# usbMIDI2CV_MC.net
KiCad netlist of a schematic drawn in EAGLE
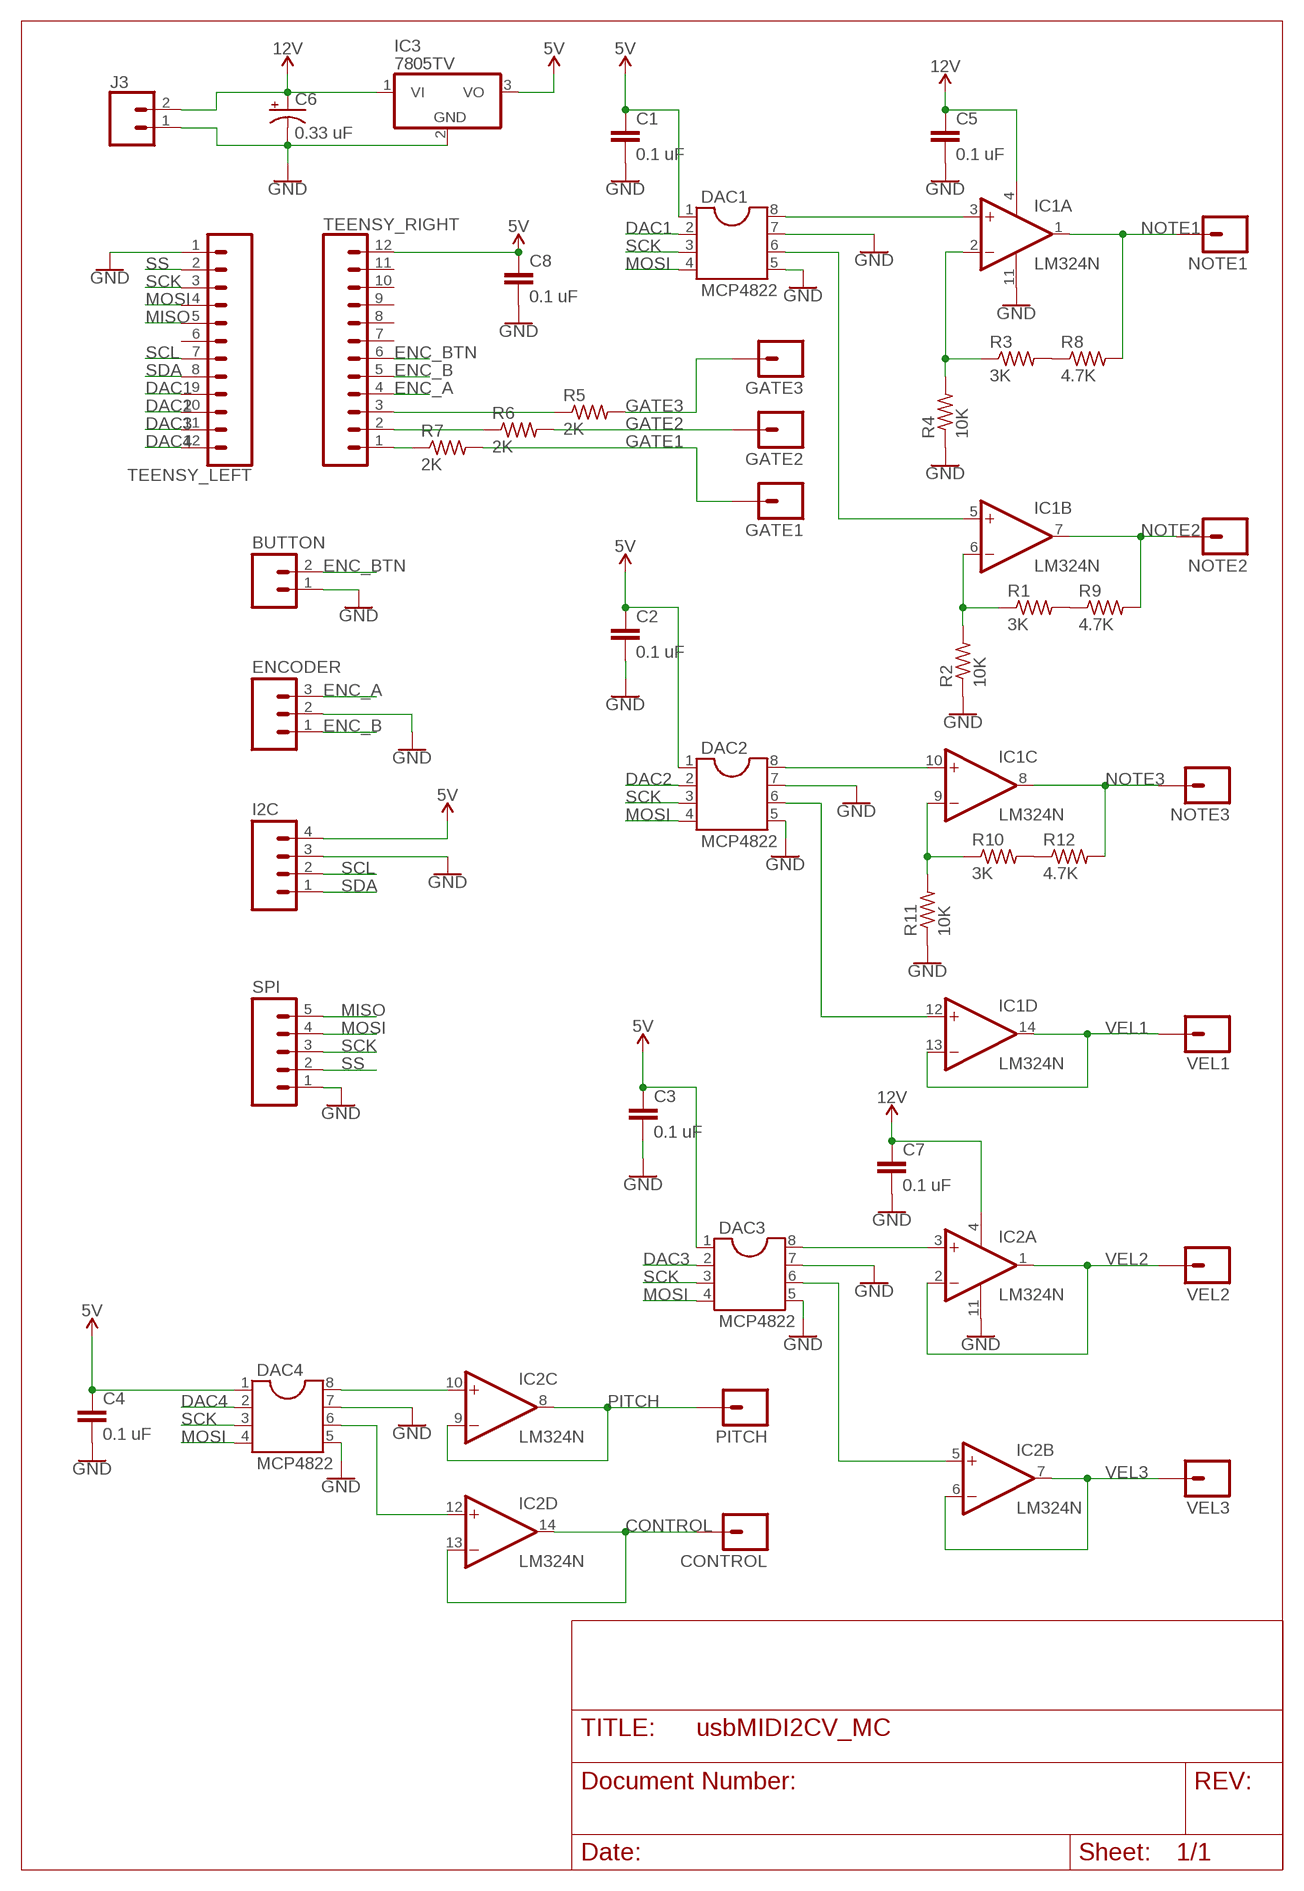
[diagram p0: schematic, sheet 1]

(export (version "E")
  (design (tool "Eeschema 10.0.6"))
  (components
    (comp (ref "BUTTON")
      (value "M02LOCK_LONGPADS")
      (footprint "eagle-import:1X02_LOCK_LONGPADS")
      (libsource (lib "eagle-import") (part "M02LOCK_LONGPADS"))
    )
    (comp (ref "C1")
      (value "0.1 uF")
      (footprint "eagle-import:CAP-PTH-SMALL")
      (libsource (lib "eagle-import") (part "CAPPTH"))
    )
    (comp (ref "C2")
      (value "0.1 uF")
      (footprint "eagle-import:CAP-PTH-SMALL")
      (libsource (lib "eagle-import") (part "CAPPTH"))
    )
    (comp (ref "C3")
      (value "0.1 uF")
      (footprint "eagle-import:CAP-PTH-SMALL")
      (libsource (lib "eagle-import") (part "CAPPTH"))
    )
    (comp (ref "C4")
      (value "0.1 uF")
      (footprint "eagle-import:CAP-PTH-SMALL")
      (libsource (lib "eagle-import") (part "CAPPTH"))
    )
    (comp (ref "C5")
      (value "0.1 uF")
      (footprint "eagle-import:CAP-PTH-SMALL")
      (libsource (lib "eagle-import") (part "CAPPTH"))
    )
    (comp (ref "C6")
      (value "0.33 uF")
      (footprint "eagle-import:CPOL-RADIAL-100UF-25V")
      (libsource (lib "eagle-import") (part "CAP_POLPTH1"))
    )
    (comp (ref "C7")
      (value "0.1 uF")
      (footprint "eagle-import:CAP-PTH-SMALL")
      (libsource (lib "eagle-import") (part "CAPPTH"))
    )
    (comp (ref "C8")
      (value "0.1 uF")
      (footprint "eagle-import:CAP-PTH-SMALL")
      (libsource (lib "eagle-import") (part "CAPPTH"))
    )
    (comp (ref "CONTROL")
      (value "M01PTH_NO_SILK_YES_STOP")
      (footprint "eagle-import:1X01_NO_SILK")
      (libsource (lib "eagle-import") (part "M01PTH_NO_SILK_YES_STOP"))
    )
    (comp (ref "DAC1")
      (value "MCP4822")
      (footprint "eagle-import:SOCKET-08")
      (libsource (lib "eagle-import") (part "DIL8S"))
    )
    (comp (ref "DAC2")
      (value "MCP4822")
      (footprint "eagle-import:SOCKET-08")
      (libsource (lib "eagle-import") (part "DIL8S"))
    )
    (comp (ref "DAC3")
      (value "MCP4822")
      (footprint "eagle-import:SOCKET-08")
      (libsource (lib "eagle-import") (part "DIL8S"))
    )
    (comp (ref "DAC4")
      (value "MCP4822")
      (footprint "eagle-import:SOCKET-08")
      (libsource (lib "eagle-import") (part "DIL8S"))
    )
    (comp (ref "ENCODER")
      (value "M03LONGPADS")
      (footprint "eagle-import:1X03_LONGPADS")
      (libsource (lib "eagle-import") (part "M03LONGPADS"))
    )
    (comp (ref "GATE1")
      (value "M01PTH_NO_SILK_YES_STOP")
      (footprint "eagle-import:1X01_NO_SILK")
      (libsource (lib "eagle-import") (part "M01PTH_NO_SILK_YES_STOP"))
    )
    (comp (ref "GATE2")
      (value "M01PTH_NO_SILK_YES_STOP")
      (footprint "eagle-import:1X01_NO_SILK")
      (libsource (lib "eagle-import") (part "M01PTH_NO_SILK_YES_STOP"))
    )
    (comp (ref "GATE3")
      (value "M01PTH_NO_SILK_YES_STOP")
      (footprint "eagle-import:1X01_NO_SILK")
      (libsource (lib "eagle-import") (part "M01PTH_NO_SILK_YES_STOP"))
    )
    (comp (ref "I2C")
      (value "M04LONGPADS")
      (footprint "eagle-import:1X04_LONGPADS")
      (libsource (lib "eagle-import") (part "M04LONGPADS"))
    )
    (comp (ref "IC1")
      (value "LM324N")
      (footprint "eagle-import:DIL14")
      (libsource (lib "eagle-import") (part "LM324N"))
    )
    (comp (ref "IC2")
      (value "LM324N")
      (footprint "eagle-import:DIL14")
      (libsource (lib "eagle-import") (part "LM324N"))
    )
    (comp (ref "IC3")
      (value "7805TV")
      (footprint "eagle-import:TO220V")
      (libsource (lib "eagle-import") (part "78TV05"))
    )
    (comp (ref "J3")
      (value "CONN_025MM")
      (footprint "eagle-import:SCREWTERMINAL-5MM-2")
      (libsource (lib "eagle-import") (part "CONN_025MM"))
    )
    (comp (ref "NOTE1")
      (value "M01PTH_NO_SILK_YES_STOP")
      (footprint "eagle-import:1X01_NO_SILK")
      (libsource (lib "eagle-import") (part "M01PTH_NO_SILK_YES_STOP"))
    )
    (comp (ref "NOTE2")
      (value "M01PTH_NO_SILK_YES_STOP")
      (footprint "eagle-import:1X01_NO_SILK")
      (libsource (lib "eagle-import") (part "M01PTH_NO_SILK_YES_STOP"))
    )
    (comp (ref "NOTE3")
      (value "M01PTH_NO_SILK_YES_STOP")
      (footprint "eagle-import:1X01_NO_SILK")
      (libsource (lib "eagle-import") (part "M01PTH_NO_SILK_YES_STOP"))
    )
    (comp (ref "PITCH")
      (value "M01PTH_NO_SILK_YES_STOP")
      (footprint "eagle-import:1X01_NO_SILK")
      (libsource (lib "eagle-import") (part "M01PTH_NO_SILK_YES_STOP"))
    )
    (comp (ref "R1")
      (value "3K")
      (footprint "eagle-import:0207_10")
      (libsource (lib "eagle-import") (part "R-US_0207/10"))
    )
    (comp (ref "R2")
      (value "10K")
      (footprint "eagle-import:0207_10")
      (libsource (lib "eagle-import") (part "R-US_0207/10"))
    )
    (comp (ref "R3")
      (value "3K")
      (footprint "eagle-import:0207_10")
      (libsource (lib "eagle-import") (part "R-US_0207/10"))
    )
    (comp (ref "R4")
      (value "10K")
      (footprint "eagle-import:0207_10")
      (libsource (lib "eagle-import") (part "R-US_0207/10"))
    )
    (comp (ref "R5")
      (value "2K")
      (footprint "eagle-import:0207_10")
      (libsource (lib "eagle-import") (part "R-US_0207/10"))
    )
    (comp (ref "R6")
      (value "2K")
      (footprint "eagle-import:0207_10")
      (libsource (lib "eagle-import") (part "R-US_0207/10"))
    )
    (comp (ref "R7")
      (value "2K")
      (footprint "eagle-import:0207_10")
      (libsource (lib "eagle-import") (part "R-US_0207/10"))
    )
    (comp (ref "R8")
      (value "4.7K")
      (footprint "eagle-import:0207_10")
      (libsource (lib "eagle-import") (part "R-US_0207/10"))
    )
    (comp (ref "R9")
      (value "4.7K")
      (footprint "eagle-import:0207_10")
      (libsource (lib "eagle-import") (part "R-US_0207/10"))
    )
    (comp (ref "R10")
      (value "3K")
      (footprint "eagle-import:0207_10")
      (libsource (lib "eagle-import") (part "R-US_0207/10"))
    )
    (comp (ref "R11")
      (value "10K")
      (footprint "eagle-import:0207_10")
      (libsource (lib "eagle-import") (part "R-US_0207/10"))
    )
    (comp (ref "R12")
      (value "4.7K")
      (footprint "eagle-import:0207_10")
      (libsource (lib "eagle-import") (part "R-US_0207/10"))
    )
    (comp (ref "SPI")
      (value "M05PTH_LONGPADS")
      (footprint "eagle-import:1X05_LONGPADS")
      (libsource (lib "eagle-import") (part "M05PTH_LONGPADS"))
    )
    (comp (ref "TEENSY_LEFT")
      (value "CONN_12")
      (footprint "eagle-import:1X12")
      (libsource (lib "eagle-import") (part "CONN_12"))
    )
    (comp (ref "TEENSY_RIGHT")
      (value "CONN_12")
      (footprint "eagle-import:1X12")
      (libsource (lib "eagle-import") (part "CONN_12"))
    )
    (comp (ref "VEL1")
      (value "M01PTH_NO_SILK_YES_STOP")
      (footprint "eagle-import:1X01_NO_SILK")
      (libsource (lib "eagle-import") (part "M01PTH_NO_SILK_YES_STOP"))
    )
    (comp (ref "VEL2")
      (value "M01PTH_NO_SILK_YES_STOP")
      (footprint "eagle-import:1X01_NO_SILK")
      (libsource (lib "eagle-import") (part "M01PTH_NO_SILK_YES_STOP"))
    )
    (comp (ref "VEL3")
      (value "M01PTH_NO_SILK_YES_STOP")
      (footprint "eagle-import:1X01_NO_SILK")
      (libsource (lib "eagle-import") (part "M01PTH_NO_SILK_YES_STOP"))
    )
  )
  (nets
    (net (code "1") (name "/CONTROL") (class "Default")
      (node (ref "CONTROL") (pin "1") (pinfunction "1_1") (pintype "passive"))
      (node (ref "IC2") (pin "13") (pinfunction "-IN_13") (pintype "input"))
      (node (ref "IC2") (pin "14") (pinfunction "OUT_14") (pintype "output"))
    )
    (net (code "2") (name "/DAC1") (class "Default")
      (node (ref "DAC1") (pin "2") (pinfunction "2_2") (pintype "passive"))
      (node (ref "TEENSY_LEFT") (pin "9") (pinfunction "9_9") (pintype "passive"))
    )
    (net (code "3") (name "/DAC2") (class "Default")
      (node (ref "DAC2") (pin "2") (pinfunction "2_2") (pintype "passive"))
      (node (ref "TEENSY_LEFT") (pin "10") (pinfunction "10_10") (pintype "passive"))
    )
    (net (code "4") (name "/DAC3") (class "Default")
      (node (ref "DAC3") (pin "2") (pinfunction "2_2") (pintype "passive"))
      (node (ref "TEENSY_LEFT") (pin "11") (pinfunction "11_11") (pintype "passive"))
    )
    (net (code "5") (name "/DAC4") (class "Default")
      (node (ref "DAC4") (pin "2") (pinfunction "2_2") (pintype "passive"))
      (node (ref "TEENSY_LEFT") (pin "12") (pinfunction "12_12") (pintype "passive"))
    )
    (net (code "6") (name "/ENC_A") (class "Default")
      (node (ref "ENCODER") (pin "3") (pinfunction "3_3") (pintype "passive"))
      (node (ref "TEENSY_RIGHT") (pin "4") (pinfunction "4_4") (pintype "passive"))
    )
    (net (code "7") (name "/ENC_B") (class "Default")
      (node (ref "ENCODER") (pin "1") (pinfunction "1_1") (pintype "passive"))
      (node (ref "TEENSY_RIGHT") (pin "5") (pinfunction "5_5") (pintype "passive"))
    )
    (net (code "8") (name "/ENC_BTN") (class "Default")
      (node (ref "BUTTON") (pin "2") (pinfunction "2_2") (pintype "passive"))
      (node (ref "TEENSY_RIGHT") (pin "6") (pinfunction "6_6") (pintype "passive"))
    )
    (net (code "9") (name "/GATE1") (class "Default")
      (node (ref "GATE1") (pin "1") (pinfunction "1_1") (pintype "passive"))
      (node (ref "R7") (pin "2") (pinfunction "2_2") (pintype "passive"))
    )
    (net (code "10") (name "/GATE2") (class "Default")
      (node (ref "GATE2") (pin "1") (pinfunction "1_1") (pintype "passive"))
      (node (ref "R6") (pin "2") (pinfunction "2_2") (pintype "passive"))
    )
    (net (code "11") (name "/GATE3") (class "Default")
      (node (ref "GATE3") (pin "1") (pinfunction "1_1") (pintype "passive"))
      (node (ref "R5") (pin "2") (pinfunction "2_2") (pintype "passive"))
    )
    (net (code "12") (name "/MISO") (class "Default")
      (node (ref "SPI") (pin "5") (pinfunction "5_5") (pintype "passive"))
      (node (ref "TEENSY_LEFT") (pin "5") (pinfunction "5_5") (pintype "passive"))
    )
    (net (code "13") (name "/MOSI") (class "Default")
      (node (ref "DAC1") (pin "4") (pinfunction "4_4") (pintype "passive"))
      (node (ref "DAC2") (pin "4") (pinfunction "4_4") (pintype "passive"))
      (node (ref "DAC3") (pin "4") (pinfunction "4_4") (pintype "passive"))
      (node (ref "DAC4") (pin "4") (pinfunction "4_4") (pintype "passive"))
      (node (ref "SPI") (pin "4") (pinfunction "4_4") (pintype "passive"))
      (node (ref "TEENSY_LEFT") (pin "4") (pinfunction "4_4") (pintype "passive"))
    )
    (net (code "14") (name "/NOTE1") (class "Default")
      (node (ref "IC1") (pin "1") (pinfunction "OUT_1") (pintype "output"))
      (node (ref "NOTE1") (pin "1") (pinfunction "1_1") (pintype "passive"))
      (node (ref "R8") (pin "2") (pinfunction "2_2") (pintype "passive"))
    )
    (net (code "15") (name "/NOTE2") (class "Default")
      (node (ref "IC1") (pin "7") (pinfunction "OUT_7") (pintype "output"))
      (node (ref "NOTE2") (pin "1") (pinfunction "1_1") (pintype "passive"))
      (node (ref "R9") (pin "2") (pinfunction "2_2") (pintype "passive"))
    )
    (net (code "16") (name "/NOTE3") (class "Default")
      (node (ref "IC1") (pin "8") (pinfunction "OUT_8") (pintype "output"))
      (node (ref "NOTE3") (pin "1") (pinfunction "1_1") (pintype "passive"))
      (node (ref "R12") (pin "2") (pinfunction "2_2") (pintype "passive"))
    )
    (net (code "17") (name "/PITCH") (class "Default")
      (node (ref "IC2") (pin "8") (pinfunction "OUT_8") (pintype "output"))
      (node (ref "IC2") (pin "9") (pinfunction "-IN_9") (pintype "input"))
      (node (ref "PITCH") (pin "1") (pinfunction "1_1") (pintype "passive"))
    )
    (net (code "18") (name "/SCK") (class "Default")
      (node (ref "DAC1") (pin "3") (pinfunction "3_3") (pintype "passive"))
      (node (ref "DAC2") (pin "3") (pinfunction "3_3") (pintype "passive"))
      (node (ref "DAC3") (pin "3") (pinfunction "3_3") (pintype "passive"))
      (node (ref "DAC4") (pin "3") (pinfunction "3_3") (pintype "passive"))
      (node (ref "SPI") (pin "3") (pinfunction "3_3") (pintype "passive"))
      (node (ref "TEENSY_LEFT") (pin "3") (pinfunction "3_3") (pintype "passive"))
    )
    (net (code "19") (name "/SCL") (class "Default")
      (node (ref "I2C") (pin "2") (pinfunction "2_2") (pintype "passive"))
      (node (ref "TEENSY_LEFT") (pin "7") (pinfunction "7_7") (pintype "passive"))
    )
    (net (code "20") (name "/SDA") (class "Default")
      (node (ref "I2C") (pin "1") (pinfunction "1_1") (pintype "passive"))
      (node (ref "TEENSY_LEFT") (pin "8") (pinfunction "8_8") (pintype "passive"))
    )
    (net (code "21") (name "/SS") (class "Default")
      (node (ref "SPI") (pin "2") (pinfunction "2_2") (pintype "passive"))
      (node (ref "TEENSY_LEFT") (pin "2") (pinfunction "2_2") (pintype "passive"))
    )
    (net (code "22") (name "/VEL1") (class "Default")
      (node (ref "IC1") (pin "13") (pinfunction "-IN_13") (pintype "input"))
      (node (ref "IC1") (pin "14") (pinfunction "OUT_14") (pintype "output"))
      (node (ref "VEL1") (pin "1") (pinfunction "1_1") (pintype "passive"))
    )
    (net (code "23") (name "/VEL2") (class "Default")
      (node (ref "IC2") (pin "1") (pinfunction "OUT_1") (pintype "output"))
      (node (ref "IC2") (pin "2") (pinfunction "-IN_2") (pintype "input"))
      (node (ref "VEL2") (pin "1") (pinfunction "1_1") (pintype "passive"))
    )
    (net (code "24") (name "/VEL3") (class "Default")
      (node (ref "IC2") (pin "6") (pinfunction "-IN_6") (pintype "input"))
      (node (ref "IC2") (pin "7") (pinfunction "OUT_7") (pintype "output"))
      (node (ref "VEL3") (pin "1") (pinfunction "1_1") (pintype "passive"))
    )
    (net (code "25") (name "5V") (class "Default")
      (node (ref "C1") (pin "1") (pinfunction "1_1") (pintype "passive"))
      (node (ref "C2") (pin "1") (pinfunction "1_1") (pintype "passive"))
      (node (ref "C3") (pin "1") (pinfunction "1_1") (pintype "passive"))
      (node (ref "C4") (pin "1") (pinfunction "1_1") (pintype "passive"))
      (node (ref "C8") (pin "1") (pinfunction "1_1") (pintype "passive"))
      (node (ref "DAC1") (pin "1") (pinfunction "1_1") (pintype "passive"))
      (node (ref "DAC2") (pin "1") (pinfunction "1_1") (pintype "passive"))
      (node (ref "DAC3") (pin "1") (pinfunction "1_1") (pintype "passive"))
      (node (ref "DAC4") (pin "1") (pinfunction "1_1") (pintype "passive"))
      (node (ref "I2C") (pin "4") (pinfunction "4_4") (pintype "passive"))
      (node (ref "IC3") (pin "3") (pinfunction "VO_3") (pintype "passive"))
      (node (ref "TEENSY_RIGHT") (pin "12") (pinfunction "12_12") (pintype "passive"))
    )
    (net (code "26") (name "12V") (class "Default")
      (node (ref "C5") (pin "1") (pinfunction "1_1") (pintype "passive"))
      (node (ref "C6") (pin "1") (pinfunction "+_1") (pintype "passive"))
      (node (ref "C7") (pin "1") (pinfunction "1_1") (pintype "passive"))
      (node (ref "IC1") (pin "4") (pinfunction "V+_4") (pintype "power_in"))
      (node (ref "IC2") (pin "4") (pinfunction "V+_4") (pintype "power_in"))
      (node (ref "IC3") (pin "1") (pinfunction "VI_1") (pintype "input"))
      (node (ref "J3") (pin "2") (pinfunction "2_2") (pintype "passive"))
    )
    (net (code "27") (name "GND") (class "Default")
      (node (ref "BUTTON") (pin "1") (pinfunction "1_1") (pintype "passive"))
      (node (ref "C1") (pin "2") (pinfunction "2_2") (pintype "passive"))
      (node (ref "C2") (pin "2") (pinfunction "2_2") (pintype "passive"))
      (node (ref "C3") (pin "2") (pinfunction "2_2") (pintype "passive"))
      (node (ref "C4") (pin "2") (pinfunction "2_2") (pintype "passive"))
      (node (ref "C5") (pin "2") (pinfunction "2_2") (pintype "passive"))
      (node (ref "C6") (pin "2") (pinfunction "-_2") (pintype "passive"))
      (node (ref "C7") (pin "2") (pinfunction "2_2") (pintype "passive"))
      (node (ref "C8") (pin "2") (pinfunction "2_2") (pintype "passive"))
      (node (ref "DAC1") (pin "5") (pinfunction "5_5") (pintype "passive"))
      (node (ref "DAC1") (pin "7") (pinfunction "7_7") (pintype "passive"))
      (node (ref "DAC2") (pin "5") (pinfunction "5_5") (pintype "passive"))
      (node (ref "DAC2") (pin "7") (pinfunction "7_7") (pintype "passive"))
      (node (ref "DAC3") (pin "5") (pinfunction "5_5") (pintype "passive"))
      (node (ref "DAC3") (pin "7") (pinfunction "7_7") (pintype "passive"))
      (node (ref "DAC4") (pin "5") (pinfunction "5_5") (pintype "passive"))
      (node (ref "DAC4") (pin "7") (pinfunction "7_7") (pintype "passive"))
      (node (ref "ENCODER") (pin "2") (pinfunction "2_2") (pintype "passive"))
      (node (ref "I2C") (pin "3") (pinfunction "3_3") (pintype "passive"))
      (node (ref "IC1") (pin "11") (pinfunction "V-_11") (pintype "power_in"))
      (node (ref "IC2") (pin "11") (pinfunction "V-_11") (pintype "power_in"))
      (node (ref "IC3") (pin "2") (pinfunction "GND_2") (pintype "passive"))
      (node (ref "J3") (pin "1") (pinfunction "1_1") (pintype "passive"))
      (node (ref "R11") (pin "1") (pinfunction "1_1") (pintype "passive"))
      (node (ref "R2") (pin "1") (pinfunction "1_1") (pintype "passive"))
      (node (ref "R4") (pin "1") (pinfunction "1_1") (pintype "passive"))
      (node (ref "SPI") (pin "1") (pinfunction "1_1") (pintype "passive"))
      (node (ref "TEENSY_LEFT") (pin "1") (pinfunction "1_1") (pintype "passive"))
    )
    (net (code "28") (name "Net-(IC1A-+IN)") (class "Default")
      (node (ref "DAC1") (pin "8") (pinfunction "8_8") (pintype "passive"))
      (node (ref "IC1") (pin "3") (pinfunction "+IN_3") (pintype "input"))
    )
    (net (code "29") (name "Net-(IC1A--IN)") (class "Default")
      (node (ref "IC1") (pin "2") (pinfunction "-IN_2") (pintype "input"))
      (node (ref "R3") (pin "1") (pinfunction "1_1") (pintype "passive"))
      (node (ref "R4") (pin "2") (pinfunction "2_2") (pintype "passive"))
    )
    (net (code "30") (name "Net-(IC1B-+IN)") (class "Default")
      (node (ref "DAC1") (pin "6") (pinfunction "6_6") (pintype "passive"))
      (node (ref "IC1") (pin "5") (pinfunction "+IN_5") (pintype "input"))
    )
    (net (code "31") (name "Net-(IC1B--IN)") (class "Default")
      (node (ref "IC1") (pin "6") (pinfunction "-IN_6") (pintype "input"))
      (node (ref "R1") (pin "1") (pinfunction "1_1") (pintype "passive"))
      (node (ref "R2") (pin "2") (pinfunction "2_2") (pintype "passive"))
    )
    (net (code "32") (name "Net-(IC1C-+IN)") (class "Default")
      (node (ref "DAC2") (pin "8") (pinfunction "8_8") (pintype "passive"))
      (node (ref "IC1") (pin "10") (pinfunction "+IN_10") (pintype "input"))
    )
    (net (code "33") (name "Net-(IC1C--IN)") (class "Default")
      (node (ref "IC1") (pin "9") (pinfunction "-IN_9") (pintype "input"))
      (node (ref "R10") (pin "1") (pinfunction "1_1") (pintype "passive"))
      (node (ref "R11") (pin "2") (pinfunction "2_2") (pintype "passive"))
    )
    (net (code "34") (name "Net-(IC1D-+IN)") (class "Default")
      (node (ref "DAC2") (pin "6") (pinfunction "6_6") (pintype "passive"))
      (node (ref "IC1") (pin "12") (pinfunction "+IN_12") (pintype "input"))
    )
    (net (code "35") (name "Net-(IC2A-+IN)") (class "Default")
      (node (ref "DAC3") (pin "8") (pinfunction "8_8") (pintype "passive"))
      (node (ref "IC2") (pin "3") (pinfunction "+IN_3") (pintype "input"))
    )
    (net (code "36") (name "Net-(IC2B-+IN)") (class "Default")
      (node (ref "DAC3") (pin "6") (pinfunction "6_6") (pintype "passive"))
      (node (ref "IC2") (pin "5") (pinfunction "+IN_5") (pintype "input"))
    )
    (net (code "37") (name "Net-(IC2C-+IN)") (class "Default")
      (node (ref "DAC4") (pin "8") (pinfunction "8_8") (pintype "passive"))
      (node (ref "IC2") (pin "10") (pinfunction "+IN_10") (pintype "input"))
    )
    (net (code "38") (name "Net-(IC2D-+IN)") (class "Default")
      (node (ref "DAC4") (pin "6") (pinfunction "6_6") (pintype "passive"))
      (node (ref "IC2") (pin "12") (pinfunction "+IN_12") (pintype "input"))
    )
    (net (code "39") (name "Net-(R1-Pad2)") (class "Default")
      (node (ref "R1") (pin "2") (pinfunction "2_2") (pintype "passive"))
      (node (ref "R9") (pin "1") (pinfunction "1_1") (pintype "passive"))
    )
    (net (code "40") (name "Net-(R3-Pad2)") (class "Default")
      (node (ref "R3") (pin "2") (pinfunction "2_2") (pintype "passive"))
      (node (ref "R8") (pin "1") (pinfunction "1_1") (pintype "passive"))
    )
    (net (code "41") (name "Net-(R5-Pad1)") (class "Default")
      (node (ref "R5") (pin "1") (pinfunction "1_1") (pintype "passive"))
      (node (ref "TEENSY_RIGHT") (pin "3") (pinfunction "3_3") (pintype "passive"))
    )
    (net (code "42") (name "Net-(R6-Pad1)") (class "Default")
      (node (ref "R6") (pin "1") (pinfunction "1_1") (pintype "passive"))
      (node (ref "TEENSY_RIGHT") (pin "2") (pinfunction "2_2") (pintype "passive"))
    )
    (net (code "43") (name "Net-(R7-Pad1)") (class "Default")
      (node (ref "R7") (pin "1") (pinfunction "1_1") (pintype "passive"))
      (node (ref "TEENSY_RIGHT") (pin "1") (pinfunction "1_1") (pintype "passive"))
    )
    (net (code "44") (name "Net-(R10-Pad2)") (class "Default")
      (node (ref "R10") (pin "2") (pinfunction "2_2") (pintype "passive"))
      (node (ref "R12") (pin "1") (pinfunction "1_1") (pintype "passive"))
    )
    (net (code "45") (name "unconnected-(TEENSY_LEFT-Pad6)") (class "Default")
      (node (ref "TEENSY_LEFT") (pin "6") (pinfunction "6_6") (pintype "passive"))
    )
    (net (code "46") (name "unconnected-(TEENSY_RIGHT-Pad7)") (class "Default")
      (node (ref "TEENSY_RIGHT") (pin "7") (pinfunction "7_7") (pintype "passive"))
    )
    (net (code "47") (name "unconnected-(TEENSY_RIGHT-Pad8)") (class "Default")
      (node (ref "TEENSY_RIGHT") (pin "8") (pinfunction "8_8") (pintype "passive"))
    )
    (net (code "48") (name "unconnected-(TEENSY_RIGHT-Pad9)") (class "Default")
      (node (ref "TEENSY_RIGHT") (pin "9") (pinfunction "9_9") (pintype "passive"))
    )
    (net (code "49") (name "unconnected-(TEENSY_RIGHT-Pad10)") (class "Default")
      (node (ref "TEENSY_RIGHT") (pin "10") (pinfunction "10_10") (pintype "passive"))
    )
    (net (code "50") (name "unconnected-(TEENSY_RIGHT-Pad11)") (class "Default")
      (node (ref "TEENSY_RIGHT") (pin "11") (pinfunction "11_11") (pintype "passive"))
    )
  )
)
